# SCH_Tracker_2023-05-21.net
KiCad netlist of a schematic drawn in EasyEDA
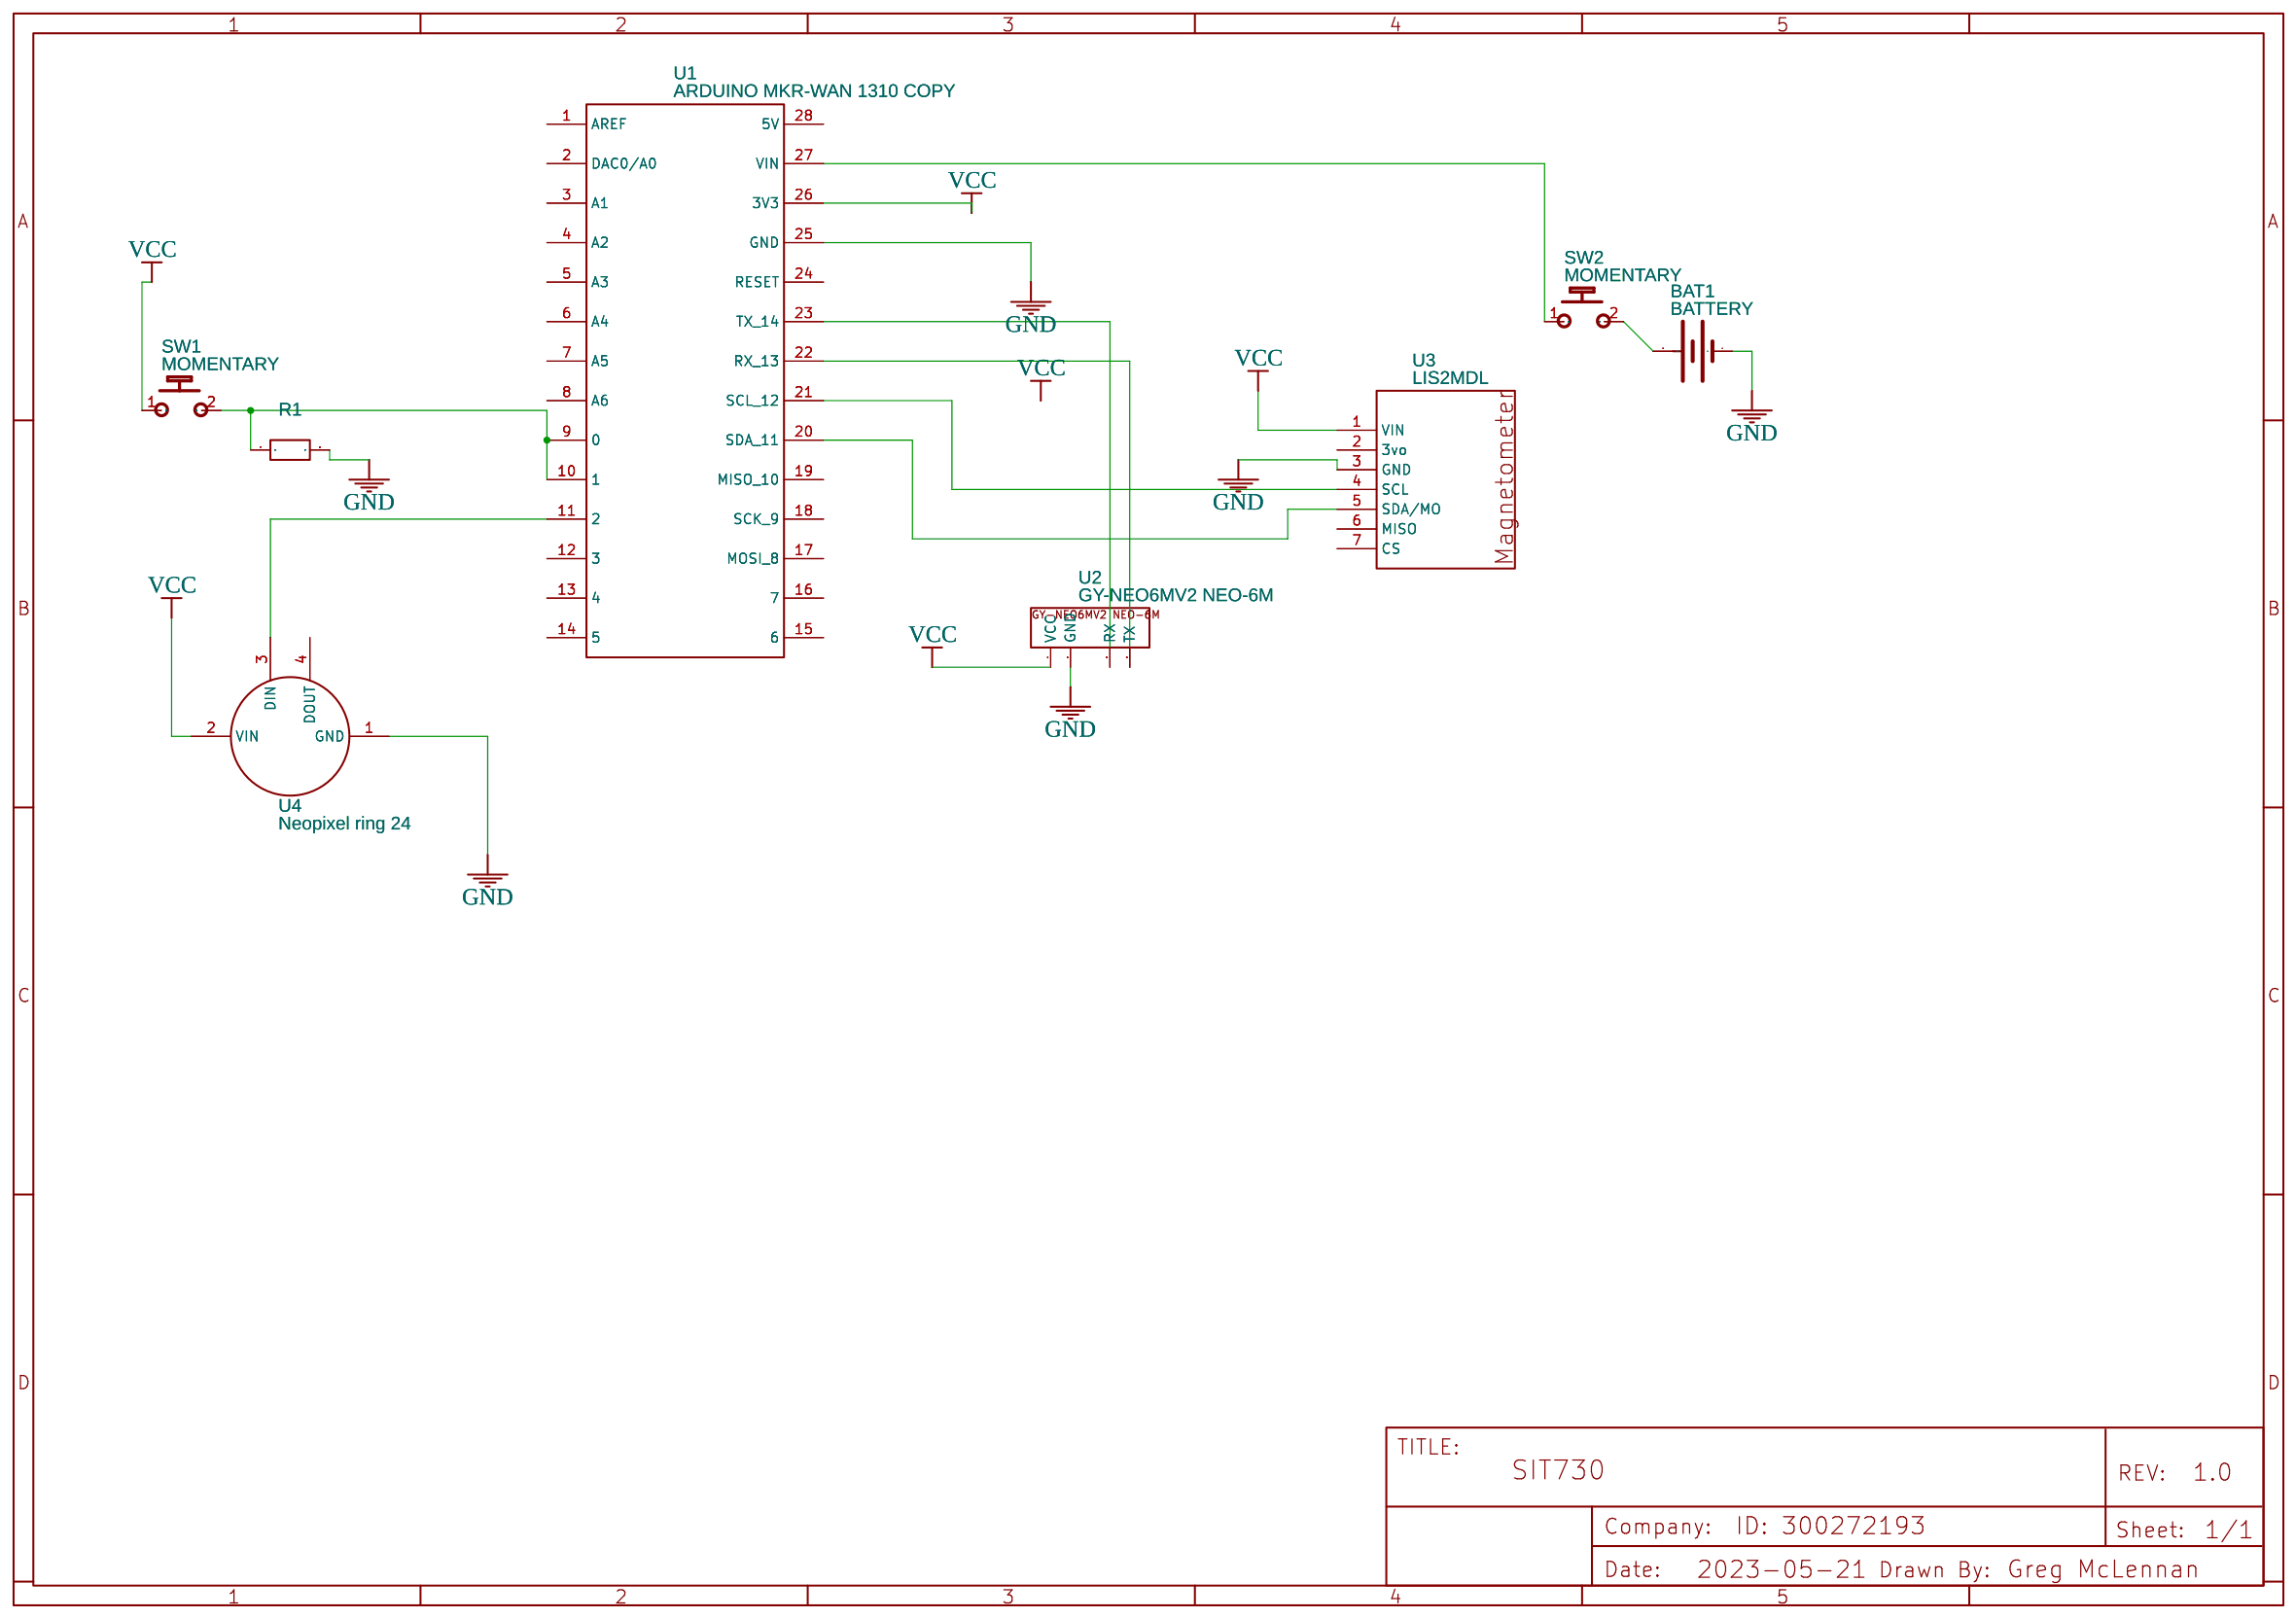
[diagram p0: schematic sheet]

(export (version "E")
  (design (tool "Eeschema 10.0.6"))
  (components
    (comp (ref "BAT1") (value "BATTERY") (libsource (lib "") (part "BATTERY")))
    (comp (ref "R1")
      (value "贴片电阻CHIPRESISTORS")
      (fields
        (field (name "BOM_Manufacturer Part") "贴片电阻ChipResistors")
        (field (name "BOM_Supplier Part") "C9900014833")
      )
      (libsource (lib "") (part "贴片电阻CHIPRESISTORS"))
    )
    (comp (ref "SW1") (value "MOMENTARY") (libsource (lib "") (part "MOMENTARY")))
    (comp (ref "SW2") (value "MOMENTARY") (libsource (lib "") (part "MOMENTARY")))
    (comp (ref "U1")
      (value "ARDUINO MKR-WAN 1310 COPY")
      (fields (field (name "BOM_Manufacturer Part") "Arduino MKR GSM 1400"))
      (libsource (lib "") (part "ARDUINO MKR-WAN 1310 COPY"))
    )
    (comp (ref "U2") (value "GY-NEO6MV2 NEO-6M") (libsource (lib "") (part "GY-NEO6MV2 NEO-6M")))
    (comp (ref "U3") (value "LIS2MDL") (libsource (lib "") (part "LIS2MDL")))
    (comp (ref "U4") (value "Neopixel ring 24") (libsource (lib "") (part "Neopixel ring 16")))
  )
  (nets
    (net (code "1") (name "GND") (class "Default")
      (node (ref "BAT1") (pin "-") (pinfunction "-_-") (pintype "passive"))
      (node (ref "R1") (pin "2") (pinfunction "2_2") (pintype "unspecified"))
      (node (ref "U1") (pin "25") (pinfunction "GND_25") (pintype "unspecified"))
      (node (ref "U2") (pin "1") (pinfunction "GND_1") (pintype "output"))
      (node (ref "U3") (pin "3") (pinfunction "GND_3") (pintype "unspecified"))
      (node (ref "U4") (pin "1") (pinfunction "GND_1") (pintype "unspecified"))
    )
    (net (code "2") (name "Net-(SW1-S)") (class "Default")
      (node (ref "R1") (pin "1") (pinfunction "1_1") (pintype "unspecified"))
      (node (ref "SW1") (pin "2") (pinfunction "S_2") (pintype "bidirectional"))
      (node (ref "U1") (pin "10") (pinfunction "1_10") (pintype "unspecified"))
      (node (ref "U1") (pin "9") (pinfunction "0_9") (pintype "unspecified"))
    )
    (net (code "3") (name "Net-(SW2-P)") (class "Default")
      (node (ref "SW2") (pin "1") (pinfunction "P_1") (pintype "bidirectional"))
      (node (ref "U1") (pin "27") (pinfunction "VIN_27") (pintype "unspecified"))
    )
    (net (code "4") (name "Net-(SW2-S)") (class "Default")
      (node (ref "BAT1") (pin "+") (pinfunction "+_+") (pintype "passive"))
      (node (ref "SW2") (pin "2") (pinfunction "S_2") (pintype "bidirectional"))
    )
    (net (code "5") (name "Net-(U1-2)") (class "Default")
      (node (ref "U1") (pin "11") (pinfunction "2_11") (pintype "unspecified"))
      (node (ref "U4") (pin "3") (pinfunction "DIN_3") (pintype "unspecified"))
    )
    (net (code "6") (name "Net-(U1-RX_13)") (class "Default")
      (node (ref "U1") (pin "22") (pinfunction "RX_13_22") (pintype "unspecified"))
      (node (ref "U2") (pin "2") (pinfunction "TX_2") (pintype "output"))
    )
    (net (code "7") (name "Net-(U1-SCL_12)") (class "Default")
      (node (ref "U1") (pin "21") (pinfunction "SCL_12_21") (pintype "unspecified"))
      (node (ref "U3") (pin "4") (pinfunction "SCL_4") (pintype "unspecified"))
    )
    (net (code "8") (name "Net-(U1-SDA_11)") (class "Default")
      (node (ref "U1") (pin "20") (pinfunction "SDA_11_20") (pintype "unspecified"))
      (node (ref "U3") (pin "5") (pinfunction "SDA/MO_5") (pintype "unspecified"))
    )
    (net (code "9") (name "Net-(U1-TX_14)") (class "Default")
      (node (ref "U1") (pin "23") (pinfunction "TX_14_23") (pintype "unspecified"))
      (node (ref "U2") (pin "3") (pinfunction "RX_3") (pintype "input"))
    )
    (net (code "10") (name "VCC") (class "Default")
      (node (ref "SW1") (pin "1") (pinfunction "P_1") (pintype "bidirectional"))
      (node (ref "U1") (pin "26") (pinfunction "3V3_26") (pintype "unspecified"))
      (node (ref "U2") (pin "4") (pinfunction "VCC_4") (pintype "passive"))
      (node (ref "U3") (pin "1") (pinfunction "VIN_1") (pintype "unspecified"))
      (node (ref "U4") (pin "2") (pinfunction "VIN_2") (pintype "unspecified"))
    )
    (net (code "11") (name "unconnected-(U1-3-Pad12)") (class "Default")
      (node (ref "U1") (pin "12") (pinfunction "3_12") (pintype "unspecified"))
    )
    (net (code "12") (name "unconnected-(U1-4-Pad13)") (class "Default")
      (node (ref "U1") (pin "13") (pinfunction "4_13") (pintype "unspecified"))
    )
    (net (code "13") (name "unconnected-(U1-5-Pad14)") (class "Default")
      (node (ref "U1") (pin "14") (pinfunction "5_14") (pintype "unspecified"))
    )
    (net (code "14") (name "unconnected-(U1-5V-Pad28)") (class "Default")
      (node (ref "U1") (pin "28") (pinfunction "5V_28") (pintype "unspecified"))
    )
    (net (code "15") (name "unconnected-(U1-6-Pad15)") (class "Default")
      (node (ref "U1") (pin "15") (pinfunction "6_15") (pintype "unspecified"))
    )
    (net (code "16") (name "unconnected-(U1-7-Pad16)") (class "Default")
      (node (ref "U1") (pin "16") (pinfunction "7_16") (pintype "unspecified"))
    )
    (net (code "17") (name "unconnected-(U1-A1-Pad3)") (class "Default")
      (node (ref "U1") (pin "3") (pinfunction "A1_3") (pintype "unspecified"))
    )
    (net (code "18") (name "unconnected-(U1-A2-Pad4)") (class "Default")
      (node (ref "U1") (pin "4") (pinfunction "A2_4") (pintype "unspecified"))
    )
    (net (code "19") (name "unconnected-(U1-A3-Pad5)") (class "Default")
      (node (ref "U1") (pin "5") (pinfunction "A3_5") (pintype "unspecified"))
    )
    (net (code "20") (name "unconnected-(U1-A4-Pad6)") (class "Default")
      (node (ref "U1") (pin "6") (pinfunction "A4_6") (pintype "unspecified"))
    )
    (net (code "21") (name "unconnected-(U1-A5-Pad7)") (class "Default")
      (node (ref "U1") (pin "7") (pinfunction "A5_7") (pintype "unspecified"))
    )
    (net (code "22") (name "unconnected-(U1-A6-Pad8)") (class "Default")
      (node (ref "U1") (pin "8") (pinfunction "A6_8") (pintype "unspecified"))
    )
    (net (code "23") (name "unconnected-(U1-AREF-Pad1)") (class "Default")
      (node (ref "U1") (pin "1") (pinfunction "AREF_1") (pintype "unspecified"))
    )
    (net (code "24") (name "unconnected-(U1-DAC0{slash}A0-Pad2)") (class "Default")
      (node (ref "U1") (pin "2") (pinfunction "DAC0/A0_2") (pintype "unspecified"))
    )
    (net (code "25") (name "unconnected-(U1-MISO_10-Pad19)") (class "Default")
      (node (ref "U1") (pin "19") (pinfunction "MISO_10_19") (pintype "unspecified"))
    )
    (net (code "26") (name "unconnected-(U1-MOSI_8-Pad17)") (class "Default")
      (node (ref "U1") (pin "17") (pinfunction "MOSI_8_17") (pintype "unspecified"))
    )
    (net (code "27") (name "unconnected-(U1-RESET-Pad24)") (class "Default")
      (node (ref "U1") (pin "24") (pinfunction "RESET_24") (pintype "unspecified"))
    )
    (net (code "28") (name "unconnected-(U1-SCK_9-Pad18)") (class "Default")
      (node (ref "U1") (pin "18") (pinfunction "SCK_9_18") (pintype "unspecified"))
    )
    (net (code "29") (name "unconnected-(U3-3vo-Pad2)") (class "Default")
      (node (ref "U3") (pin "2") (pinfunction "3vo_2") (pintype "unspecified"))
    )
    (net (code "30") (name "unconnected-(U3-CS-Pad7)") (class "Default")
      (node (ref "U3") (pin "7") (pinfunction "CS_7") (pintype "unspecified"))
    )
    (net (code "31") (name "unconnected-(U3-MISO-Pad6)") (class "Default")
      (node (ref "U3") (pin "6") (pinfunction "MISO_6") (pintype "unspecified"))
    )
    (net (code "32") (name "unconnected-(U4-DOUT-Pad4)") (class "Default")
      (node (ref "U4") (pin "4") (pinfunction "DOUT_4") (pintype "unspecified"))
    )
  )
)
